# v9_d_w_USB.net
KiCad netlist of a schematic drawn in EasyEDA Pro
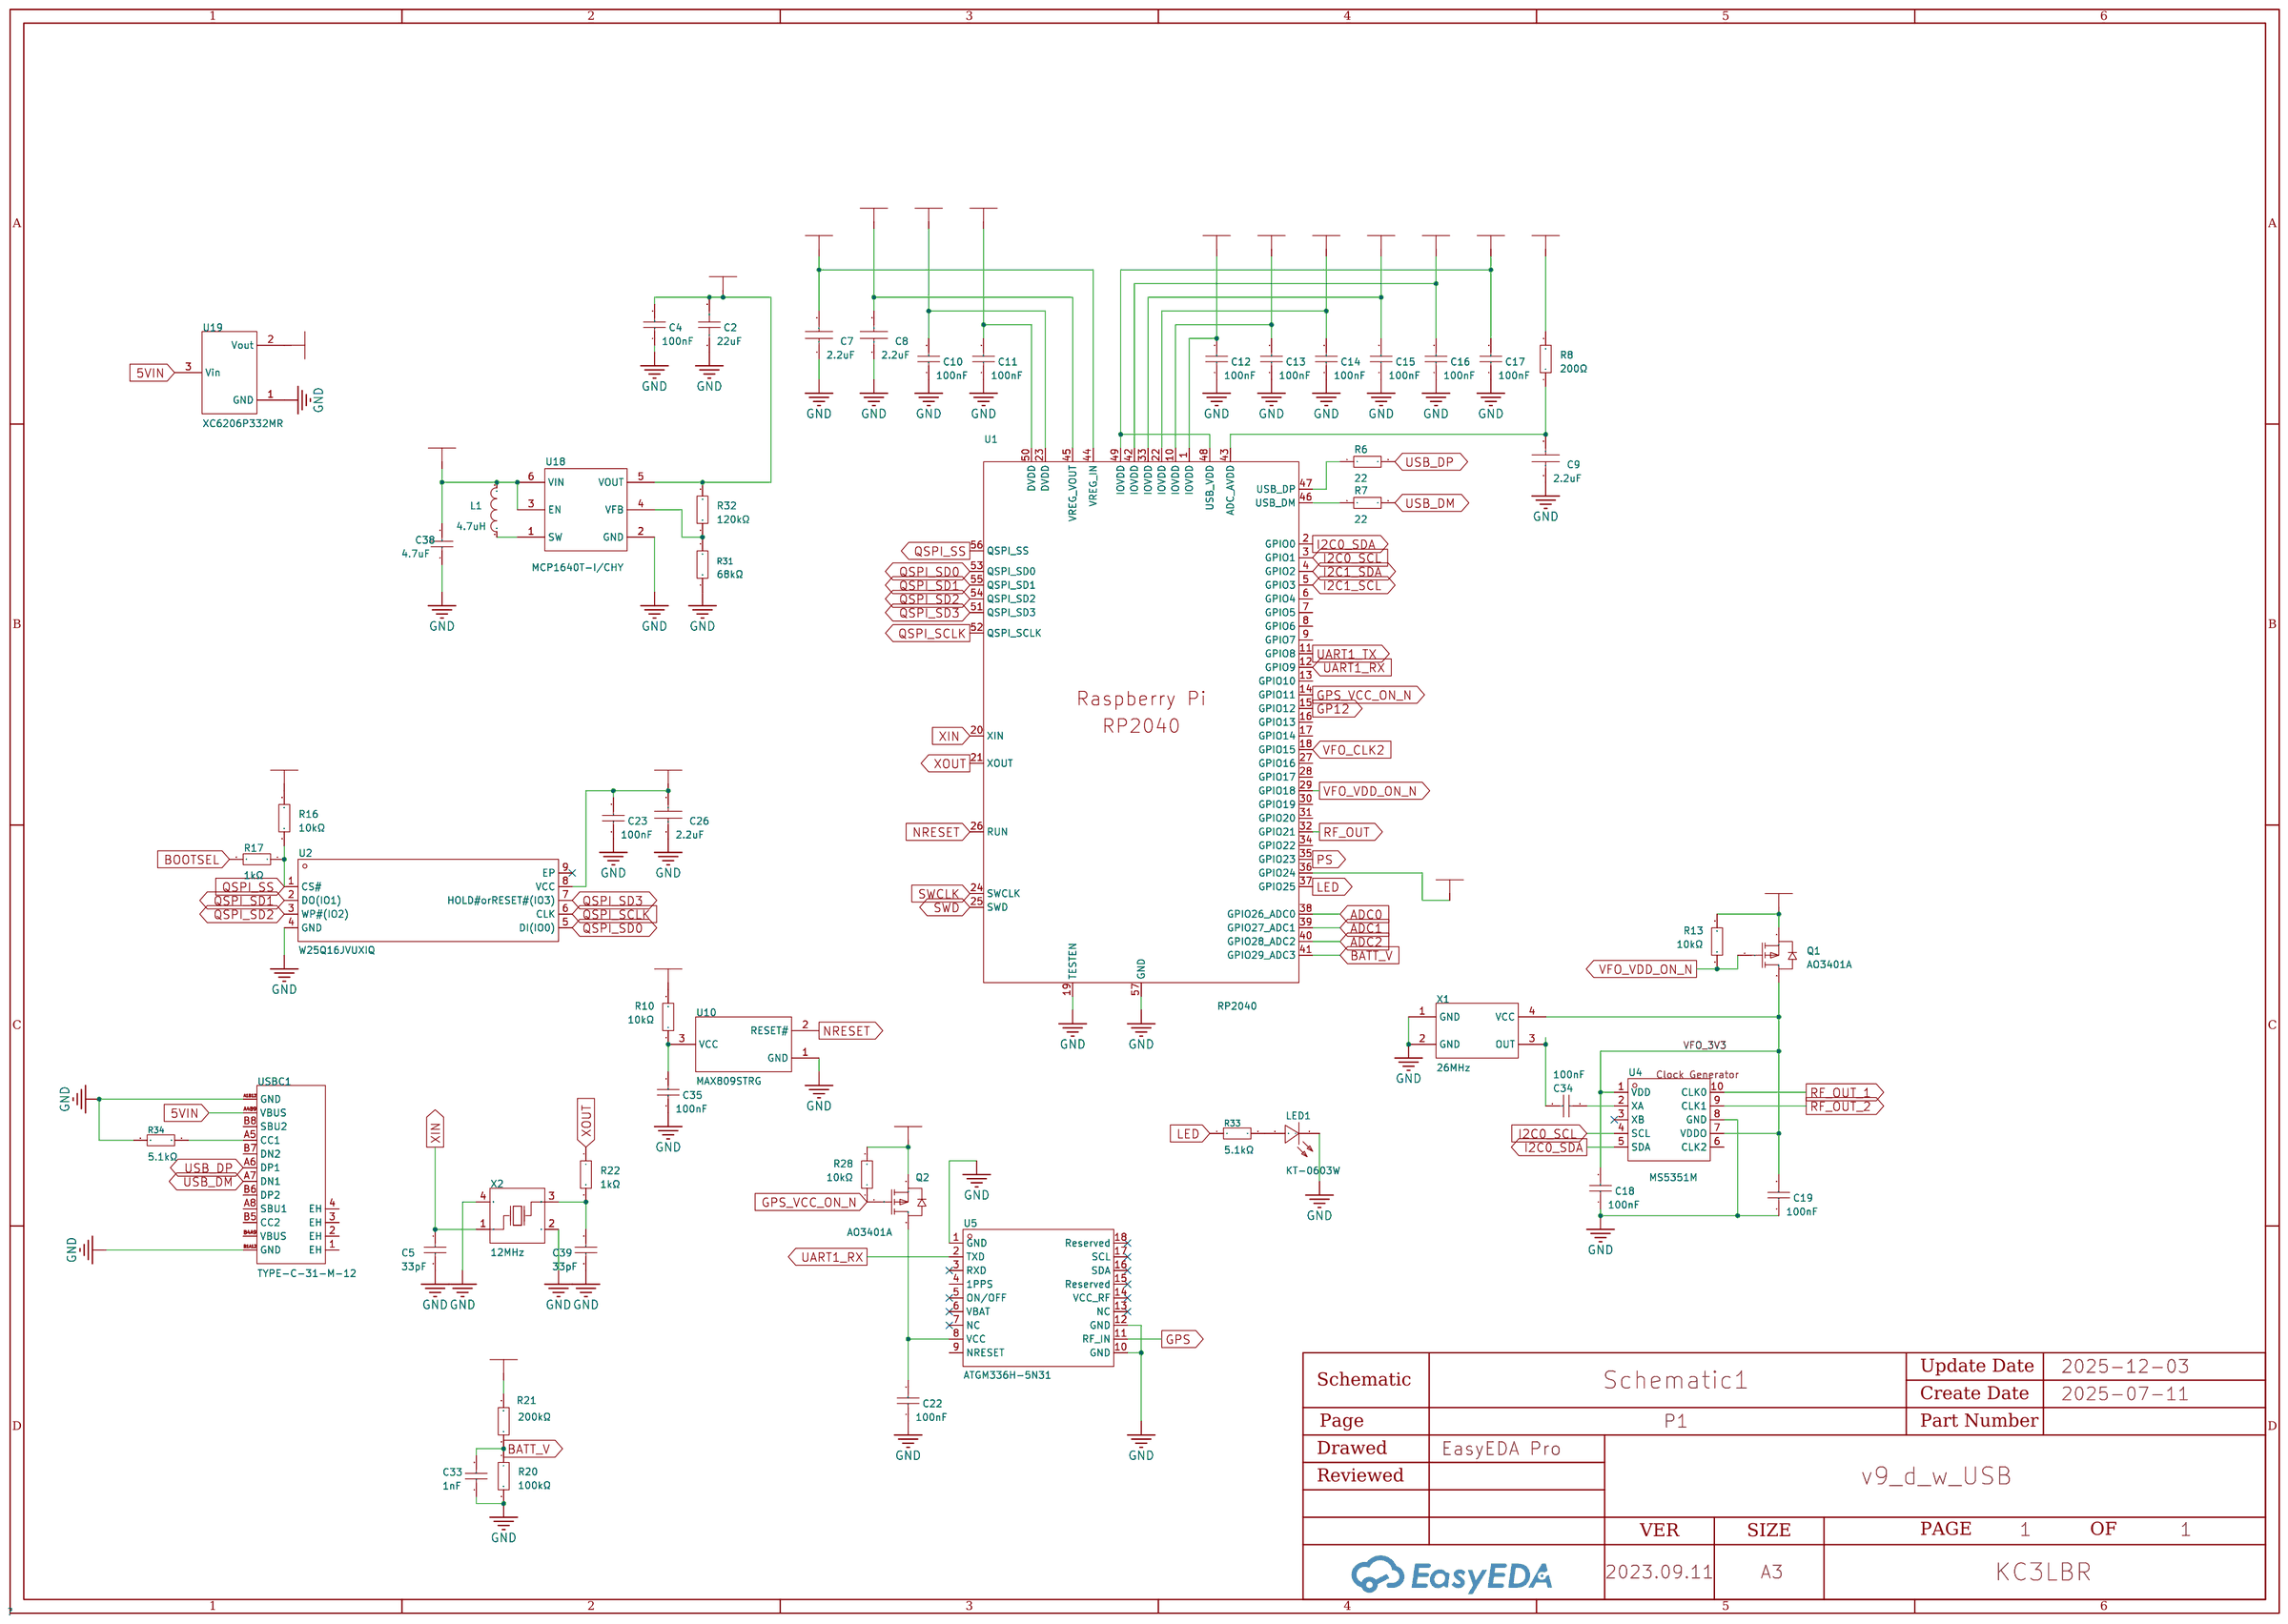
[diagram p0: schematic sheet]

(export (version "E")
  (design (tool "Eeschema 10.0.6"))
  (components
    (comp (ref "C2")
      (value "22uF")
      (footprint "easyedapro:C0603")
      (fields
        (field (name "Manufacturer Part") "CL10A226MQ8NRNC")
        (field (name "Manufacturer") "SAMSUNG(三星)")
      )
      (libsource (lib "easyedapro") (part "CL10A226MQ8NRNC"))
    )
    (comp (ref "C4")
      (value "100nF")
      (footprint "easyedapro:C0402_NEW")
      (fields
        (field (name "Manufacturer Part") "CL05B104KO5NNNC")
        (field (name "Manufacturer") "SAMSUNG(三星)")
      )
      (libsource (lib "easyedapro") (part "CL05B104KO5NNNC"))
    )
    (comp (ref "C5")
      (value "33pF")
      (footprint "easyedapro:C0402")
      (fields (field (name "Manufacturer Part") "0402CG330J500NT") (field (name "Manufacturer") "FH(风华)"))
      (libsource (lib "easyedapro") (part "0402CG330J500NT"))
    )
    (comp (ref "C7")
      (value "2.2uF")
      (footprint "easyedapro:C0402")
      (fields
        (field (name "Manufacturer Part") "CL05A225MQ5NSNC")
        (field (name "Manufacturer") "SAMSUNG(三星)")
      )
      (libsource (lib "easyedapro") (part "CL05A225MQ5NSNC"))
    )
    (comp (ref "C8")
      (value "2.2uF")
      (footprint "easyedapro:C0402")
      (fields
        (field (name "Manufacturer Part") "CL05A225MQ5NSNC")
        (field (name "Manufacturer") "SAMSUNG(三星)")
      )
      (libsource (lib "easyedapro") (part "CL05A225MQ5NSNC"))
    )
    (comp (ref "C9")
      (value "2.2uF")
      (footprint "easyedapro:C0402")
      (fields
        (field (name "Manufacturer Part") "CL05A225MQ5NSNC")
        (field (name "Manufacturer") "SAMSUNG(三星)")
      )
      (libsource (lib "easyedapro") (part "CL05A225MQ5NSNC"))
    )
    (comp (ref "C10")
      (value "100nF")
      (footprint "easyedapro:C0402_NEW")
      (fields
        (field (name "Manufacturer Part") "CL05B104KO5NNNC")
        (field (name "Manufacturer") "SAMSUNG(三星)")
      )
      (libsource (lib "easyedapro") (part "CL05B104KO5NNNC"))
    )
    (comp (ref "C11")
      (value "100nF")
      (footprint "easyedapro:C0402_NEW")
      (fields
        (field (name "Manufacturer Part") "CL05B104KO5NNNC")
        (field (name "Manufacturer") "SAMSUNG(三星)")
      )
      (libsource (lib "easyedapro") (part "CL05B104KO5NNNC"))
    )
    (comp (ref "C12")
      (value "100nF")
      (footprint "easyedapro:C0402_NEW")
      (fields
        (field (name "Manufacturer Part") "CL05B104KO5NNNC")
        (field (name "Manufacturer") "SAMSUNG(三星)")
      )
      (libsource (lib "easyedapro") (part "CL05B104KO5NNNC"))
    )
    (comp (ref "C13")
      (value "100nF")
      (footprint "easyedapro:C0402_NEW")
      (fields
        (field (name "Manufacturer Part") "CL05B104KO5NNNC")
        (field (name "Manufacturer") "SAMSUNG(三星)")
      )
      (libsource (lib "easyedapro") (part "CL05B104KO5NNNC"))
    )
    (comp (ref "C14")
      (value "100nF")
      (footprint "easyedapro:C0402_NEW")
      (fields
        (field (name "Manufacturer Part") "CL05B104KO5NNNC")
        (field (name "Manufacturer") "SAMSUNG(三星)")
      )
      (libsource (lib "easyedapro") (part "CL05B104KO5NNNC"))
    )
    (comp (ref "C15")
      (value "100nF")
      (footprint "easyedapro:C0402_NEW")
      (fields
        (field (name "Manufacturer Part") "CL05B104KO5NNNC")
        (field (name "Manufacturer") "SAMSUNG(三星)")
      )
      (libsource (lib "easyedapro") (part "CL05B104KO5NNNC"))
    )
    (comp (ref "C16")
      (value "100nF")
      (footprint "easyedapro:C0402_NEW")
      (fields
        (field (name "Manufacturer Part") "CL05B104KO5NNNC")
        (field (name "Manufacturer") "SAMSUNG(三星)")
      )
      (libsource (lib "easyedapro") (part "CL05B104KO5NNNC"))
    )
    (comp (ref "C17")
      (value "100nF")
      (footprint "easyedapro:C0402_NEW")
      (fields
        (field (name "Manufacturer Part") "CL05B104KO5NNNC")
        (field (name "Manufacturer") "SAMSUNG(三星)")
      )
      (libsource (lib "easyedapro") (part "CL05B104KO5NNNC"))
    )
    (comp (ref "C18")
      (value "100nF")
      (footprint "easyedapro:C0402_NEW")
      (fields
        (field (name "Manufacturer Part") "CL05B104KO5NNNC")
        (field (name "Manufacturer") "SAMSUNG(三星)")
      )
      (libsource (lib "easyedapro") (part "CL05B104KO5NNNC"))
    )
    (comp (ref "C19")
      (value "100nF")
      (footprint "easyedapro:C0402_NEW")
      (fields
        (field (name "Manufacturer Part") "CL05B104KO5NNNC")
        (field (name "Manufacturer") "SAMSUNG(三星)")
      )
      (libsource (lib "easyedapro") (part "CL05B104KO5NNNC"))
    )
    (comp (ref "C22")
      (value "100nF")
      (footprint "easyedapro:C0402_NEW")
      (fields
        (field (name "Manufacturer Part") "CL05B104KO5NNNC")
        (field (name "Manufacturer") "SAMSUNG(三星)")
      )
      (libsource (lib "easyedapro") (part "CL05B104KO5NNNC"))
    )
    (comp (ref "C23")
      (value "100nF")
      (footprint "easyedapro:C0402_NEW")
      (fields
        (field (name "Manufacturer Part") "CL05B104KO5NNNC")
        (field (name "Manufacturer") "SAMSUNG(三星)")
      )
      (libsource (lib "easyedapro") (part "CL05B104KO5NNNC"))
    )
    (comp (ref "C26")
      (value "2.2uF")
      (footprint "easyedapro:C0402")
      (fields
        (field (name "Manufacturer Part") "CL05A225MQ5NSNC")
        (field (name "Manufacturer") "SAMSUNG(三星)")
      )
      (libsource (lib "easyedapro") (part "CL05A225MQ5NSNC"))
    )
    (comp (ref "C33")
      (value "1nF")
      (footprint "easyedapro:C0402")
      (fields (field (name "Manufacturer Part") "0402B102K500NT") (field (name "Manufacturer") "FH(风华)"))
      (libsource (lib "easyedapro") (part "0402B102K500NT"))
    )
    (comp (ref "C34")
      (value "100nF")
      (footprint "easyedapro:C0402_NEW")
      (fields
        (field (name "Manufacturer Part") "CL05B104KO5NNNC")
        (field (name "Manufacturer") "SAMSUNG(三星)")
      )
      (libsource (lib "easyedapro") (part "CL05B104KO5NNNC"))
    )
    (comp (ref "C35")
      (value "100nF")
      (footprint "easyedapro:C0402_NEW")
      (fields
        (field (name "Manufacturer Part") "CL05B104KO5NNNC")
        (field (name "Manufacturer") "SAMSUNG(三星)")
      )
      (libsource (lib "easyedapro") (part "CL05B104KO5NNNC"))
    )
    (comp (ref "C38")
      (value "4.7uF")
      (footprint "easyedapro:C0603")
      (fields
        (field (name "Manufacturer Part") "CL10A475KO8NNNC")
        (field (name "Manufacturer") "SAMSUNG(三星)")
      )
      (libsource (lib "easyedapro") (part "CL10A475KO8NNNC"))
    )
    (comp (ref "C39")
      (value "33pF")
      (footprint "easyedapro:C0402")
      (fields (field (name "Manufacturer Part") "0402CG330J500NT") (field (name "Manufacturer") "FH(风华)"))
      (libsource (lib "easyedapro") (part "0402CG330J500NT"))
    )
    (comp (ref "L1")
      (value "4.7uH")
      (footprint "easyedapro:IND-SMD_L2.5-W1.8")
      (fields
        (field (name "Manufacturer Part") "CBC2518T4R7M")
        (field (name "Manufacturer") "TAIYO YUDEN(太诱)")
      )
      (libsource (lib "easyedapro") (part "CBC2518T4R7M"))
    )
    (comp (ref "LED1")
      (value "KT-0603W")
      (footprint "easyedapro:LED0603-R-RD_WHITE")
      (fields (field (name "Manufacturer") "KENTO"))
      (libsource (lib "easyedapro") (part "0603White light_C2290"))
    )
    (comp (ref "Q1")
      (value "AO3401A")
      (footprint "easyedapro:SOT-23_L2.9-W1.3-P1.90-LS2.4-BR")
      (fields (field (name "Manufacturer") "AOS"))
      (libsource (lib "easyedapro") (part "AO3401A"))
    )
    (comp (ref "Q2")
      (value "AO3401A")
      (footprint "easyedapro:SOT-23_L2.9-W1.3-P1.90-LS2.4-BR")
      (fields (field (name "Manufacturer") "AOS"))
      (libsource (lib "easyedapro") (part "AO3401A"))
    )
    (comp (ref "R6")
      (value "22")
      (footprint "easyedapro:R0402")
      (fields
        (field (name "Manufacturer Part") "0402WGF220JTCE")
        (field (name "Manufacturer") "UNI-ROYAL(厚声)")
      )
      (libsource (lib "easyedapro") (part "0402WGF220JTCE"))
    )
    (comp (ref "R7")
      (value "22")
      (footprint "easyedapro:R0402")
      (fields
        (field (name "Manufacturer Part") "0402WGF220JTCE")
        (field (name "Manufacturer") "UNI-ROYAL(厚声)")
      )
      (libsource (lib "easyedapro") (part "0402WGF220JTCE"))
    )
    (comp (ref "R8")
      (value "200Ω")
      (footprint "easyedapro:R0402")
      (fields
        (field (name "Manufacturer Part") "0402WGF2000TCE")
        (field (name "Manufacturer") "UNI-ROYAL(厚声)")
      )
      (libsource (lib "easyedapro") (part "0402WGF2000TCE"))
    )
    (comp (ref "R10")
      (value "10kΩ")
      (footprint "easyedapro:R0402")
      (fields
        (field (name "Manufacturer Part") "0402WGF1002TCE")
        (field (name "Manufacturer") "UNI-ROYAL(厚声)")
      )
      (libsource (lib "easyedapro") (part "0402WGF1002TCE"))
    )
    (comp (ref "R13")
      (value "10kΩ")
      (footprint "easyedapro:R0402")
      (fields
        (field (name "Manufacturer Part") "0402WGF1002TCE")
        (field (name "Manufacturer") "UNI-ROYAL(厚声)")
      )
      (libsource (lib "easyedapro") (part "0402WGF1002TCE"))
    )
    (comp (ref "R16")
      (value "10kΩ")
      (footprint "easyedapro:R0402")
      (fields
        (field (name "Manufacturer Part") "0402WGF1002TCE")
        (field (name "Manufacturer") "UNI-ROYAL(厚声)")
      )
      (libsource (lib "easyedapro") (part "0402WGF1002TCE"))
    )
    (comp (ref "R17")
      (value "1kΩ")
      (footprint "easyedapro:R0402")
      (fields
        (field (name "Manufacturer Part") "0402WGF1001TCE")
        (field (name "Manufacturer") "UNI-ROYAL(厚声)")
      )
      (libsource (lib "easyedapro") (part "0402WGF1001TCE"))
    )
    (comp (ref "R20")
      (value "100kΩ")
      (footprint "easyedapro:R0402")
      (fields
        (field (name "Manufacturer Part") "0402WGF1003TCE")
        (field (name "Manufacturer") "UNI-ROYAL(厚声)")
      )
      (libsource (lib "easyedapro") (part "0402WGF1003TCE"))
    )
    (comp (ref "R21")
      (value "200kΩ")
      (footprint "easyedapro:R0402")
      (fields
        (field (name "Manufacturer Part") "0402WGF2003TCE")
        (field (name "Manufacturer") "UNI-ROYAL(厚声)")
      )
      (libsource (lib "easyedapro") (part "0402WGF2003TCE"))
    )
    (comp (ref "R22")
      (value "1kΩ")
      (footprint "easyedapro:R0402")
      (fields
        (field (name "Manufacturer Part") "0402WGF1001TCE")
        (field (name "Manufacturer") "UNI-ROYAL(厚声)")
      )
      (libsource (lib "easyedapro") (part "0402WGF1001TCE"))
    )
    (comp (ref "R28")
      (value "10kΩ")
      (footprint "easyedapro:R0402")
      (fields
        (field (name "Manufacturer Part") "0402WGF1002TCE")
        (field (name "Manufacturer") "UNI-ROYAL(厚声)")
      )
      (libsource (lib "easyedapro") (part "0402WGF1002TCE"))
    )
    (comp (ref "R31")
      (value "68kΩ")
      (footprint "easyedapro:R0603")
      (fields
        (field (name "Manufacturer Part") "0603WAF6802T5E")
        (field (name "Manufacturer") "UNI-ROYAL(厚声)")
      )
      (libsource (lib "easyedapro") (part "0603WAF6802T5E"))
    )
    (comp (ref "R32")
      (value "120kΩ")
      (footprint "easyedapro:R0603")
      (fields
        (field (name "Manufacturer Part") "0603WAF1203T5E")
        (field (name "Manufacturer") "UNI-ROYAL(厚声)")
      )
      (libsource (lib "easyedapro") (part "0603WAF1203T5E"))
    )
    (comp (ref "R33")
      (value "5.1kΩ")
      (footprint "easyedapro:R0402")
      (fields
        (field (name "Manufacturer Part") "0402WGF5101TCE")
        (field (name "Manufacturer") "UNI-ROYAL(厚声)")
      )
      (libsource (lib "easyedapro") (part "0402WGF5101TCE"))
    )
    (comp (ref "R34")
      (value "5.1kΩ")
      (footprint "easyedapro:R0402")
      (fields
        (field (name "Manufacturer Part") "0402WGF5101TCE")
        (field (name "Manufacturer") "UNI-ROYAL(厚声)")
      )
      (libsource (lib "easyedapro") (part "0402WGF5101TCE"))
    )
    (comp (ref "U1")
      (value "RP2040")
      (footprint "easyedapro:LQFN-56_L7.0-W7.0-P0.4-EP")
      (fields (field (name "Manufacturer") "Raspberry Pi(树莓派)"))
      (libsource (lib "easyedapro") (part "RP2040"))
    )
    (comp (ref "U2")
      (value "W25Q16JVUXIQ")
      (footprint "easyedapro:USON-8_L3.0-W2.0-P0.50-BL-EP")
      (fields (field (name "Manufacturer") "WINBOND(华邦)"))
      (libsource (lib "easyedapro") (part "W25Q16JVUXIQ"))
    )
    (comp (ref "U4")
      (value "MS5351M")
      (footprint "easyedapro:MSOP-10_L3.0-W3.0-P0.50-LS5.0-BL")
      (description "Clock Generator")
      (fields (field (name "Manufacturer") "杭州瑞盟"))
      (libsource (lib "easyedapro") (part "MS5351M"))
    )
    (comp (ref "U5")
      (value "ATGM336H-5N31")
      (footprint "easyedapro:GPSM-SMD_ATGM336H-TR")
      (fields (field (name "Manufacturer") "杭州中科微"))
      (libsource (lib "easyedapro") (part "ATGM336H-5N31"))
    )
    (comp (ref "U10")
      (value "MAX809STRG")
      (footprint "easyedapro:SOT-23-3_L2.9-W1.6-P1.90-LS2.8-BR")
      (fields (field (name "Manufacturer") "onsemi(安森美)"))
      (libsource (lib "easyedapro") (part "MAX809STRG"))
    )
    (comp (ref "U18")
      (value "MCP1640T-I/CHY")
      (footprint "easyedapro:SOT-23-6_L2.9-W1.6-P0.95-LS2.8-BR")
      (fields (field (name "Manufacturer") "MICROCHIP(美国微芯)"))
      (libsource (lib "easyedapro") (part "MCP1640T-I/CHY"))
    )
    (comp (ref "U19")
      (value "XC6206P332MR")
      (footprint "easyedapro:SOT-23-3_L2.9-W1.6-P1.90-LS2.8-BR")
      (fields (field (name "Manufacturer") "TOREX(特瑞仕)"))
      (libsource (lib "easyedapro") (part "XC6206P332MR"))
    )
    (comp (ref "USBC1")
      (value "TYPE-C-31-M-12")
      (footprint "easyedapro:USB-C_SMD-TYPE-C-31-M-12_1")
      (fields (field (name "Manufacturer") "韩国韩荣"))
      (libsource (lib "easyedapro") (part "TYPE-C-31-M-12"))
    )
    (comp (ref "X1")
      (value "26MHz")
      (footprint "easyedapro:OSC-SMD_4P-L2.5-W2.0-BL")
      (fields (field (name "Manufacturer Part") "1XXB26000MAA") (field (name "Manufacturer") "KDS(大真空)"))
      (libsource (lib "easyedapro") (part "1XXB26000MAA"))
    )
    (comp (ref "X2")
      (value "12MHz")
      (footprint "easyedapro:OSC-SMD_4P-L3.2-W2.5-BL")
      (fields (field (name "Manufacturer Part") "X322512MSB4SI") (field (name "Manufacturer") "YXC(扬兴晶振)"))
      (libsource (lib "easyedapro") (part "X322512MSB4SI"))
    )
  )
  (nets
    (net (code "1") (name "/VFO_3V3") (class "Default")
      (node (ref "C18") (pin "2") (pinfunction "2_2") (pintype "input"))
      (node (ref "C19") (pin "2") (pinfunction "2_2") (pintype "input"))
      (node (ref "Q1") (pin "3") (pinfunction "D_3") (pintype "input"))
      (node (ref "U4") (pin "1") (pinfunction "VDD_1") (pintype "input"))
      (node (ref "U4") (pin "7") (pinfunction "VDDO_7") (pintype "input"))
      (node (ref "X1") (pin "4") (pinfunction "VCC_4") (pintype "input"))
    )
    (net (code "2") (name "1V1") (class "Default")
      (node (ref "C10") (pin "2") (pinfunction "2_2") (pintype "input"))
      (node (ref "C11") (pin "2") (pinfunction "2_2") (pintype "input"))
      (node (ref "C8") (pin "2") (pinfunction "2_2") (pintype "input"))
      (node (ref "U1") (pin "23") (pinfunction "DVDD_23") (pintype "bidirectional"))
      (node (ref "U1") (pin "45") (pinfunction "VREG_VOUT_45") (pintype "bidirectional"))
      (node (ref "U1") (pin "50") (pinfunction "DVDD_50") (pintype "bidirectional"))
    )
    (net (code "3") (name "3V3") (class "Default")
      (node (ref "C12") (pin "2") (pinfunction "2_2") (pintype "input"))
      (node (ref "C13") (pin "2") (pinfunction "2_2") (pintype "input"))
      (node (ref "C14") (pin "2") (pinfunction "2_2") (pintype "input"))
      (node (ref "C15") (pin "2") (pinfunction "2_2") (pintype "input"))
      (node (ref "C16") (pin "2") (pinfunction "2_2") (pintype "input"))
      (node (ref "C17") (pin "2") (pinfunction "2_2") (pintype "input"))
      (node (ref "C2") (pin "2") (pinfunction "2_2") (pintype "input"))
      (node (ref "C23") (pin "2") (pinfunction "2_2") (pintype "input"))
      (node (ref "C26") (pin "2") (pinfunction "2_2") (pintype "input"))
      (node (ref "C4") (pin "2") (pinfunction "2_2") (pintype "input"))
      (node (ref "C7") (pin "2") (pinfunction "2_2") (pintype "input"))
      (node (ref "Q1") (pin "2") (pinfunction "S_2") (pintype "input"))
      (node (ref "Q2") (pin "2") (pinfunction "S_2") (pintype "input"))
      (node (ref "R10") (pin "2") (pinfunction "2_2") (pintype "input"))
      (node (ref "R13") (pin "2") (pinfunction "2_2") (pintype "input"))
      (node (ref "R16") (pin "2") (pinfunction "2_2") (pintype "input"))
      (node (ref "R28") (pin "2") (pinfunction "2_2") (pintype "input"))
      (node (ref "R32") (pin "2") (pinfunction "2_2") (pintype "input"))
      (node (ref "R8") (pin "2") (pinfunction "2_2") (pintype "input"))
      (node (ref "U1") (pin "1") (pinfunction "IOVDD_1") (pintype "bidirectional"))
      (node (ref "U1") (pin "10") (pinfunction "IOVDD_10") (pintype "bidirectional"))
      (node (ref "U1") (pin "22") (pinfunction "IOVDD_22") (pintype "bidirectional"))
      (node (ref "U1") (pin "33") (pinfunction "IOVDD_33") (pintype "bidirectional"))
      (node (ref "U1") (pin "36") (pinfunction "GPIO24_36") (pintype "bidirectional"))
      (node (ref "U1") (pin "42") (pinfunction "IOVDD_42") (pintype "bidirectional"))
      (node (ref "U1") (pin "44") (pinfunction "VREG_IN_44") (pintype "bidirectional"))
      (node (ref "U1") (pin "48") (pinfunction "USB_VDD_48") (pintype "bidirectional"))
      (node (ref "U1") (pin "49") (pinfunction "IOVDD_49") (pintype "bidirectional"))
      (node (ref "U18") (pin "5") (pinfunction "VOUT_5") (pintype "input"))
      (node (ref "U2") (pin "8") (pinfunction "VCC_8") (pintype "input"))
    )
    (net (code "4") (name "5VIN") (class "Default")
      (node (ref "U19") (pin "3") (pinfunction "Vin_3") (pintype "unspecified"))
      (node (ref "USBC1") (pin "A4B9") (pinfunction "VBUS_A4B9") (pintype "unspecified"))
    )
    (net (code "5") (name "ADC0") (class "Default")
      (node (ref "U1") (pin "38") (pinfunction "GPIO26_ADC0_38") (pintype "bidirectional"))
    )
    (net (code "6") (name "ADC1") (class "Default")
      (node (ref "U1") (pin "39") (pinfunction "GPIO27_ADC1_39") (pintype "bidirectional"))
    )
    (net (code "7") (name "ADC2") (class "Default")
      (node (ref "U1") (pin "40") (pinfunction "GPIO28_ADC2_40") (pintype "bidirectional"))
    )
    (net (code "8") (name "BATT_V") (class "Default")
      (node (ref "C33") (pin "2") (pinfunction "2_2") (pintype "input"))
      (node (ref "R20") (pin "1") (pinfunction "1_1") (pintype "input"))
      (node (ref "R21") (pin "1") (pinfunction "1_1") (pintype "input"))
      (node (ref "U1") (pin "41") (pinfunction "GPIO29_ADC3_41") (pintype "bidirectional"))
    )
    (net (code "9") (name "BOOTSEL") (class "Default")
      (node (ref "R17") (pin "2") (pinfunction "2_2") (pintype "input"))
    )
    (net (code "10") (name "GND") (class "Default")
      (node (ref "C10") (pin "1") (pinfunction "1_1") (pintype "input"))
      (node (ref "C11") (pin "1") (pinfunction "1_1") (pintype "input"))
      (node (ref "C12") (pin "1") (pinfunction "1_1") (pintype "input"))
      (node (ref "C13") (pin "1") (pinfunction "1_1") (pintype "input"))
      (node (ref "C14") (pin "1") (pinfunction "1_1") (pintype "input"))
      (node (ref "C15") (pin "1") (pinfunction "1_1") (pintype "input"))
      (node (ref "C16") (pin "1") (pinfunction "1_1") (pintype "input"))
      (node (ref "C17") (pin "1") (pinfunction "1_1") (pintype "input"))
      (node (ref "C18") (pin "1") (pinfunction "1_1") (pintype "input"))
      (node (ref "C19") (pin "1") (pinfunction "1_1") (pintype "input"))
      (node (ref "C2") (pin "1") (pinfunction "1_1") (pintype "input"))
      (node (ref "C22") (pin "1") (pinfunction "1_1") (pintype "input"))
      (node (ref "C23") (pin "1") (pinfunction "1_1") (pintype "input"))
      (node (ref "C26") (pin "1") (pinfunction "1_1") (pintype "input"))
      (node (ref "C33") (pin "1") (pinfunction "1_1") (pintype "input"))
      (node (ref "C35") (pin "1") (pinfunction "1_1") (pintype "input"))
      (node (ref "C38") (pin "1") (pinfunction "1_1") (pintype "input"))
      (node (ref "C39") (pin "1") (pinfunction "1_1") (pintype "input"))
      (node (ref "C4") (pin "1") (pinfunction "1_1") (pintype "input"))
      (node (ref "C5") (pin "1") (pinfunction "1_1") (pintype "input"))
      (node (ref "C7") (pin "1") (pinfunction "1_1") (pintype "input"))
      (node (ref "C8") (pin "1") (pinfunction "1_1") (pintype "input"))
      (node (ref "C9") (pin "1") (pinfunction "1_1") (pintype "input"))
      (node (ref "LED1") (pin "2") (pinfunction "K_2") (pintype "unspecified"))
      (node (ref "R20") (pin "2") (pinfunction "2_2") (pintype "input"))
      (node (ref "R31") (pin "1") (pinfunction "1_1") (pintype "input"))
      (node (ref "R34") (pin "1") (pinfunction "1_1") (pintype "input"))
      (node (ref "U1") (pin "19") (pinfunction "TESTEN_19") (pintype "input"))
      (node (ref "U1") (pin "57") (pinfunction "GND_57") (pintype "bidirectional"))
      (node (ref "U10") (pin "1") (pinfunction "GND_1") (pintype "input"))
      (node (ref "U18") (pin "2") (pinfunction "GND_2") (pintype "input"))
      (node (ref "U19") (pin "1") (pinfunction "GND_1") (pintype "unspecified"))
      (node (ref "U2") (pin "4") (pinfunction "GND_4") (pintype "input"))
      (node (ref "U4") (pin "8") (pinfunction "GND_8") (pintype "input"))
      (node (ref "U5") (pin "1") (pinfunction "GND_1") (pintype "input"))
      (node (ref "U5") (pin "10") (pinfunction "GND_10") (pintype "input"))
      (node (ref "U5") (pin "12") (pinfunction "GND_12") (pintype "input"))
      (node (ref "USBC1") (pin "A1B12") (pinfunction "GND_A1B12") (pintype "unspecified"))
      (node (ref "USBC1") (pin "B1A12") (pinfunction "GND_B1A12") (pintype "unspecified"))
      (node (ref "X1") (pin "1") (pinfunction "GND_1") (pintype "input"))
      (node (ref "X1") (pin "2") (pinfunction "GND_2") (pintype "input"))
      (node (ref "X2") (pin "2") (pinfunction "GND_2") (pintype "input"))
      (node (ref "X2") (pin "4") (pinfunction "GND_4") (pintype "input"))
    )
    (net (code "11") (name "GP12") (class "Default")
      (node (ref "U1") (pin "15") (pinfunction "GPIO12_15") (pintype "bidirectional"))
    )
    (net (code "12") (name "GPS") (class "Default")
      (node (ref "U5") (pin "11") (pinfunction "RF_IN_11") (pintype "input"))
    )
    (net (code "13") (name "GPS_VCC_ON_N") (class "Default")
      (node (ref "Q2") (pin "1") (pinfunction "G_1") (pintype "input"))
      (node (ref "R28") (pin "1") (pinfunction "1_1") (pintype "input"))
      (node (ref "U1") (pin "14") (pinfunction "GPIO11_14") (pintype "bidirectional"))
    )
    (net (code "14") (name "I2C0_SCL") (class "Default")
      (node (ref "U1") (pin "3") (pinfunction "GPIO1_3") (pintype "bidirectional"))
      (node (ref "U4") (pin "4") (pinfunction "SCL_4") (pintype "input"))
    )
    (net (code "15") (name "I2C0_SDA") (class "Default")
      (node (ref "U1") (pin "2") (pinfunction "GPIO0_2") (pintype "bidirectional"))
      (node (ref "U4") (pin "5") (pinfunction "SDA_5") (pintype "input"))
    )
    (net (code "16") (name "I2C1_SCL") (class "Default")
      (node (ref "U1") (pin "5") (pinfunction "GPIO3_5") (pintype "bidirectional"))
    )
    (net (code "17") (name "I2C1_SDA") (class "Default")
      (node (ref "U1") (pin "4") (pinfunction "GPIO2_4") (pintype "bidirectional"))
    )
    (net (code "18") (name "LED") (class "Default")
      (node (ref "R33") (pin "1") (pinfunction "1_1") (pintype "input"))
      (node (ref "U1") (pin "37") (pinfunction "GPIO25_37") (pintype "bidirectional"))
    )
    (net (code "19") (name "NRESET") (class "Default")
      (node (ref "U1") (pin "26") (pinfunction "RUN_26") (pintype "input"))
      (node (ref "U10") (pin "2") (pinfunction "RESET#_2") (pintype "input"))
    )
    (net (code "20") (name "Net-(LED1-A)") (class "Default")
      (node (ref "LED1") (pin "1") (pinfunction "A_1") (pintype "unspecified"))
      (node (ref "R33") (pin "2") (pinfunction "2_2") (pintype "input"))
    )
    (net (code "21") (name "Net-(Q2-D)") (class "Default")
      (node (ref "C22") (pin "2") (pinfunction "2_2") (pintype "input"))
      (node (ref "Q2") (pin "3") (pinfunction "D_3") (pintype "input"))
      (node (ref "U5") (pin "8") (pinfunction "VCC_8") (pintype "input"))
    )
    (net (code "22") (name "Net-(U1-ADC_AVDD)") (class "Default")
      (node (ref "C9") (pin "2") (pinfunction "2_2") (pintype "input"))
      (node (ref "R8") (pin "1") (pinfunction "1_1") (pintype "input"))
      (node (ref "U1") (pin "43") (pinfunction "ADC_AVDD_43") (pintype "bidirectional"))
    )
    (net (code "23") (name "Net-(U1-USB_DM)") (class "Default")
      (node (ref "R7") (pin "1") (pinfunction "1_1") (pintype "input"))
      (node (ref "U1") (pin "46") (pinfunction "USB_DM_46") (pintype "bidirectional"))
    )
    (net (code "24") (name "Net-(U1-USB_DP)") (class "Default")
      (node (ref "R6") (pin "1") (pinfunction "1_1") (pintype "input"))
      (node (ref "U1") (pin "47") (pinfunction "USB_DP_47") (pintype "bidirectional"))
    )
    (net (code "25") (name "Net-(U4-XA)") (class "Default")
      (node (ref "C34") (pin "1") (pinfunction "1_1") (pintype "input"))
      (node (ref "U4") (pin "2") (pinfunction "XA_2") (pintype "input"))
    )
    (net (code "26") (name "Net-(U10-VCC)") (class "Default")
      (node (ref "C35") (pin "2") (pinfunction "2_2") (pintype "input"))
      (node (ref "R10") (pin "1") (pinfunction "1_1") (pintype "input"))
      (node (ref "U10") (pin "3") (pinfunction "VCC_3") (pintype "input"))
    )
    (net (code "27") (name "Net-(U18-SW)") (class "Default")
      (node (ref "L1") (pin "1") (pinfunction "1_1") (pintype "input"))
      (node (ref "U18") (pin "1") (pinfunction "SW_1") (pintype "input"))
    )
    (net (code "28") (name "Net-(U18-VFB)") (class "Default")
      (node (ref "R31") (pin "2") (pinfunction "2_2") (pintype "input"))
      (node (ref "R32") (pin "1") (pinfunction "1_1") (pintype "input"))
      (node (ref "U18") (pin "4") (pinfunction "VFB_4") (pintype "input"))
    )
    (net (code "29") (name "Net-(USBC1-CC1)") (class "Default")
      (node (ref "R34") (pin "2") (pinfunction "2_2") (pintype "input"))
      (node (ref "USBC1") (pin "A5") (pinfunction "CC1_A5") (pintype "unspecified"))
    )
    (net (code "30") (name "Net-(X1-OUT)") (class "Default")
      (node (ref "C34") (pin "2") (pinfunction "2_2") (pintype "input"))
      (node (ref "X1") (pin "3") (pinfunction "OUT_3") (pintype "input"))
    )
    (net (code "31") (name "Net-(X2-OSC2)") (class "Default")
      (node (ref "C39") (pin "2") (pinfunction "2_2") (pintype "input"))
      (node (ref "R22") (pin "2") (pinfunction "2_2") (pintype "input"))
      (node (ref "X2") (pin "3") (pinfunction "OSC2_3") (pintype "input"))
    )
    (net (code "32") (name "PS") (class "Default")
      (node (ref "U1") (pin "35") (pinfunction "GPIO23_35") (pintype "bidirectional"))
    )
    (net (code "33") (name "QSPI_SCLK") (class "Default")
      (node (ref "U1") (pin "52") (pinfunction "QSPI_SCLK_52") (pintype "output"))
      (node (ref "U2") (pin "6") (pinfunction "CLK_6") (pintype "input"))
    )
    (net (code "34") (name "QSPI_SD0") (class "Default")
      (node (ref "U1") (pin "53") (pinfunction "QSPI_SD0_53") (pintype "bidirectional"))
      (node (ref "U2") (pin "5") (pinfunction "DI(IO0)_5") (pintype "input"))
    )
    (net (code "35") (name "QSPI_SD1") (class "Default")
      (node (ref "U1") (pin "55") (pinfunction "QSPI_SD1_55") (pintype "bidirectional"))
      (node (ref "U2") (pin "2") (pinfunction "DO(IO1)_2") (pintype "input"))
    )
    (net (code "36") (name "QSPI_SD2") (class "Default")
      (node (ref "U1") (pin "54") (pinfunction "QSPI_SD2_54") (pintype "bidirectional"))
      (node (ref "U2") (pin "3") (pinfunction "WP#(IO2)_3") (pintype "input"))
    )
    (net (code "37") (name "QSPI_SD3") (class "Default")
      (node (ref "U1") (pin "51") (pinfunction "QSPI_SD3_51") (pintype "bidirectional"))
      (node (ref "U2") (pin "7") (pinfunction "HOLD#orRESET#(IO3)_7") (pintype "input"))
    )
    (net (code "38") (name "QSPI_SS") (class "Default")
      (node (ref "R16") (pin "1") (pinfunction "1_1") (pintype "input"))
      (node (ref "R17") (pin "1") (pinfunction "1_1") (pintype "input"))
      (node (ref "U1") (pin "56") (pinfunction "QSPI_SS_56") (pintype "bidirectional"))
      (node (ref "U2") (pin "1") (pinfunction "CS#_1") (pintype "input"))
    )
    (net (code "39") (name "RF_OUT") (class "Default")
      (node (ref "U1") (pin "32") (pinfunction "GPIO21_32") (pintype "bidirectional"))
    )
    (net (code "40") (name "RF_OUT_1") (class "Default")
      (node (ref "U4") (pin "10") (pinfunction "CLK0_10") (pintype "input"))
    )
    (net (code "41") (name "RF_OUT_2") (class "Default")
      (node (ref "U4") (pin "9") (pinfunction "CLK1_9") (pintype "input"))
    )
    (net (code "42") (name "SWCLK") (class "Default")
      (node (ref "U1") (pin "24") (pinfunction "SWCLK_24") (pintype "output"))
    )
    (net (code "43") (name "SWD") (class "Default")
      (node (ref "U1") (pin "25") (pinfunction "SWD_25") (pintype "bidirectional"))
    )
    (net (code "44") (name "UART1_RX") (class "Default")
      (node (ref "U1") (pin "12") (pinfunction "GPIO9_12") (pintype "bidirectional"))
      (node (ref "U5") (pin "2") (pinfunction "TXD_2") (pintype "input"))
    )
    (net (code "45") (name "UART1_TX") (class "Default")
      (node (ref "U1") (pin "11") (pinfunction "GPIO8_11") (pintype "bidirectional"))
    )
    (net (code "46") (name "USB_DM") (class "Default")
      (node (ref "R7") (pin "2") (pinfunction "2_2") (pintype "input"))
      (node (ref "USBC1") (pin "A7") (pinfunction "DN1_A7") (pintype "unspecified"))
    )
    (net (code "47") (name "USB_DP") (class "Default")
      (node (ref "R6") (pin "2") (pinfunction "2_2") (pintype "input"))
      (node (ref "USBC1") (pin "A6") (pinfunction "DP1_A6") (pintype "unspecified"))
    )
    (net (code "48") (name "VBUS") (class "Default")
      (node (ref "C38") (pin "2") (pinfunction "2_2") (pintype "input"))
      (node (ref "L1") (pin "2") (pinfunction "2_2") (pintype "input"))
      (node (ref "R21") (pin "2") (pinfunction "2_2") (pintype "input"))
      (node (ref "U18") (pin "3") (pinfunction "EN_3") (pintype "input"))
      (node (ref "U18") (pin "6") (pinfunction "VIN_6") (pintype "input"))
      (node (ref "U19") (pin "2") (pinfunction "Vout_2") (pintype "unspecified"))
    )
    (net (code "49") (name "VFO_CLK2") (class "Default")
      (node (ref "U1") (pin "18") (pinfunction "GPIO15_18") (pintype "bidirectional"))
    )
    (net (code "50") (name "VFO_VDD_ON_N") (class "Default")
      (node (ref "Q1") (pin "1") (pinfunction "G_1") (pintype "input"))
      (node (ref "R13") (pin "1") (pinfunction "1_1") (pintype "input"))
      (node (ref "U1") (pin "29") (pinfunction "GPIO18_29") (pintype "bidirectional"))
    )
    (net (code "51") (name "XIN") (class "Default")
      (node (ref "C5") (pin "2") (pinfunction "2_2") (pintype "input"))
      (node (ref "U1") (pin "20") (pinfunction "XIN_20") (pintype "input"))
      (node (ref "X2") (pin "1") (pinfunction "OSC1_1") (pintype "input"))
    )
    (net (code "52") (name "XOUT") (class "Default")
      (node (ref "R22") (pin "1") (pinfunction "1_1") (pintype "input"))
      (node (ref "U1") (pin "21") (pinfunction "XOUT_21") (pintype "input"))
    )
    (net (code "53") (name "unconnected-(U1-GPIO4-Pad6)") (class "Default")
      (node (ref "U1") (pin "6") (pinfunction "GPIO4_6") (pintype "bidirectional"))
    )
    (net (code "54") (name "unconnected-(U1-GPIO5-Pad7)") (class "Default")
      (node (ref "U1") (pin "7") (pinfunction "GPIO5_7") (pintype "bidirectional"))
    )
    (net (code "55") (name "unconnected-(U1-GPIO6-Pad8)") (class "Default")
      (node (ref "U1") (pin "8") (pinfunction "GPIO6_8") (pintype "bidirectional"))
    )
    (net (code "56") (name "unconnected-(U1-GPIO7-Pad9)") (class "Default")
      (node (ref "U1") (pin "9") (pinfunction "GPIO7_9") (pintype "bidirectional"))
    )
    (net (code "57") (name "unconnected-(U1-GPIO10-Pad13)") (class "Default")
      (node (ref "U1") (pin "13") (pinfunction "GPIO10_13") (pintype "bidirectional"))
    )
    (net (code "58") (name "unconnected-(U1-GPIO13-Pad16)") (class "Default")
      (node (ref "U1") (pin "16") (pinfunction "GPIO13_16") (pintype "bidirectional"))
    )
    (net (code "59") (name "unconnected-(U1-GPIO14-Pad17)") (class "Default")
      (node (ref "U1") (pin "17") (pinfunction "GPIO14_17") (pintype "bidirectional"))
    )
    (net (code "60") (name "unconnected-(U1-GPIO16-Pad27)") (class "Default")
      (node (ref "U1") (pin "27") (pinfunction "GPIO16_27") (pintype "bidirectional"))
    )
    (net (code "61") (name "unconnected-(U1-GPIO17-Pad28)") (class "Default")
      (node (ref "U1") (pin "28") (pinfunction "GPIO17_28") (pintype "bidirectional"))
    )
    (net (code "62") (name "unconnected-(U1-GPIO19-Pad30)") (class "Default")
      (node (ref "U1") (pin "30") (pinfunction "GPIO19_30") (pintype "bidirectional"))
    )
    (net (code "63") (name "unconnected-(U1-GPIO20-Pad31)") (class "Default")
      (node (ref "U1") (pin "31") (pinfunction "GPIO20_31") (pintype "bidirectional"))
    )
    (net (code "64") (name "unconnected-(U1-GPIO22-Pad34)") (class "Default")
      (node (ref "U1") (pin "34") (pinfunction "GPIO22_34") (pintype "bidirectional"))
    )
    (net (code "65") (name "unconnected-(U2-EP-Pad9)") (class "Default")
      (node (ref "U2") (pin "9") (pinfunction "EP_9") (pintype "input+no_connect"))
    )
    (net (code "66") (name "unconnected-(U4-CLK2-Pad6)") (class "Default")
      (node (ref "U4") (pin "6") (pinfunction "CLK2_6") (pintype "input"))
    )
    (net (code "67") (name "unconnected-(U4-XB-Pad3)") (class "Default")
      (node (ref "U4") (pin "3") (pinfunction "XB_3") (pintype "input+no_connect"))
    )
    (net (code "68") (name "unconnected-(U5-1PPS-Pad4)") (class "Default")
      (node (ref "U5") (pin "4") (pinfunction "1PPS_4") (pintype "input"))
    )
    (net (code "69") (name "unconnected-(U5-NC-Pad7)") (class "Default")
      (node (ref "U5") (pin "7") (pinfunction "NC_7") (pintype "input+no_connect"))
    )
    (net (code "70") (name "unconnected-(U5-NC-Pad13)") (class "Default")
      (node (ref "U5") (pin "13") (pinfunction "NC_13") (pintype "input+no_connect"))
    )
    (net (code "71") (name "unconnected-(U5-NRESET-Pad9)") (class "Default")
      (node (ref "U5") (pin "9") (pinfunction "NRESET_9") (pintype "input"))
    )
    (net (code "72") (name "unconnected-(U5-ON{slash}OFF-Pad5)") (class "Default")
      (node (ref "U5") (pin "5") (pinfunction "ON/OFF_5") (pintype "input+no_connect"))
    )
    (net (code "73") (name "unconnected-(U5-RXD-Pad3)") (class "Default")
      (node (ref "U5") (pin "3") (pinfunction "RXD_3") (pintype "input+no_connect"))
    )
    (net (code "74") (name "unconnected-(U5-Reserved-Pad15)") (class "Default")
      (node (ref "U5") (pin "15") (pinfunction "Reserved_15") (pintype "input+no_connect"))
    )
    (net (code "75") (name "unconnected-(U5-Reserved-Pad18)") (class "Default")
      (node (ref "U5") (pin "18") (pinfunction "Reserved_18") (pintype "input+no_connect"))
    )
    (net (code "76") (name "unconnected-(U5-SCL-Pad17)") (class "Default")
      (node (ref "U5") (pin "17") (pinfunction "SCL_17") (pintype "input+no_connect"))
    )
    (net (code "77") (name "unconnected-(U5-SDA-Pad16)") (class "Default")
      (node (ref "U5") (pin "16") (pinfunction "SDA_16") (pintype "input+no_connect"))
    )
    (net (code "78") (name "unconnected-(U5-VBAT-Pad6)") (class "Default")
      (node (ref "U5") (pin "6") (pinfunction "VBAT_6") (pintype "input+no_connect"))
    )
    (net (code "79") (name "unconnected-(U5-VCC_RF-Pad14)") (class "Default")
      (node (ref "U5") (pin "14") (pinfunction "VCC_RF_14") (pintype "input+no_connect"))
    )
    (net (code "80") (name "unconnected-(USBC1-CC2-PadB5)") (class "Default")
      (node (ref "USBC1") (pin "B5") (pinfunction "CC2_B5") (pintype "unspecified"))
    )
    (net (code "81") (name "unconnected-(USBC1-DN2-PadB7)") (class "Default")
      (node (ref "USBC1") (pin "B7") (pinfunction "DN2_B7") (pintype "unspecified"))
    )
    (net (code "82") (name "unconnected-(USBC1-DP2-PadB6)") (class "Default")
      (node (ref "USBC1") (pin "B6") (pinfunction "DP2_B6") (pintype "unspecified"))
    )
    (net (code "83") (name "unconnected-(USBC1-EH-Pad1)") (class "Default")
      (node (ref "USBC1") (pin "1") (pinfunction "EH_1") (pintype "unspecified"))
    )
    (net (code "84") (name "unconnected-(USBC1-EH-Pad2)") (class "Default")
      (node (ref "USBC1") (pin "2") (pinfunction "EH_2") (pintype "unspecified"))
    )
    (net (code "85") (name "unconnected-(USBC1-EH-Pad3)") (class "Default")
      (node (ref "USBC1") (pin "3") (pinfunction "EH_3") (pintype "unspecified"))
    )
    (net (code "86") (name "unconnected-(USBC1-EH-Pad4)") (class "Default")
      (node (ref "USBC1") (pin "4") (pinfunction "EH_4") (pintype "unspecified"))
    )
    (net (code "87") (name "unconnected-(USBC1-SBU1-PadA8)") (class "Default")
      (node (ref "USBC1") (pin "A8") (pinfunction "SBU1_A8") (pintype "unspecified"))
    )
    (net (code "88") (name "unconnected-(USBC1-SBU2-PadB8)") (class "Default")
      (node (ref "USBC1") (pin "B8") (pinfunction "SBU2_B8") (pintype "unspecified"))
    )
    (net (code "89") (name "unconnected-(USBC1-VBUS-PadB4A9)") (class "Default")
      (node (ref "USBC1") (pin "B4A9") (pinfunction "VBUS_B4A9") (pintype "unspecified"))
    )
  )
)
